# main_schematic.net
KiCad netlist of a schematic drawn in Altium Designer
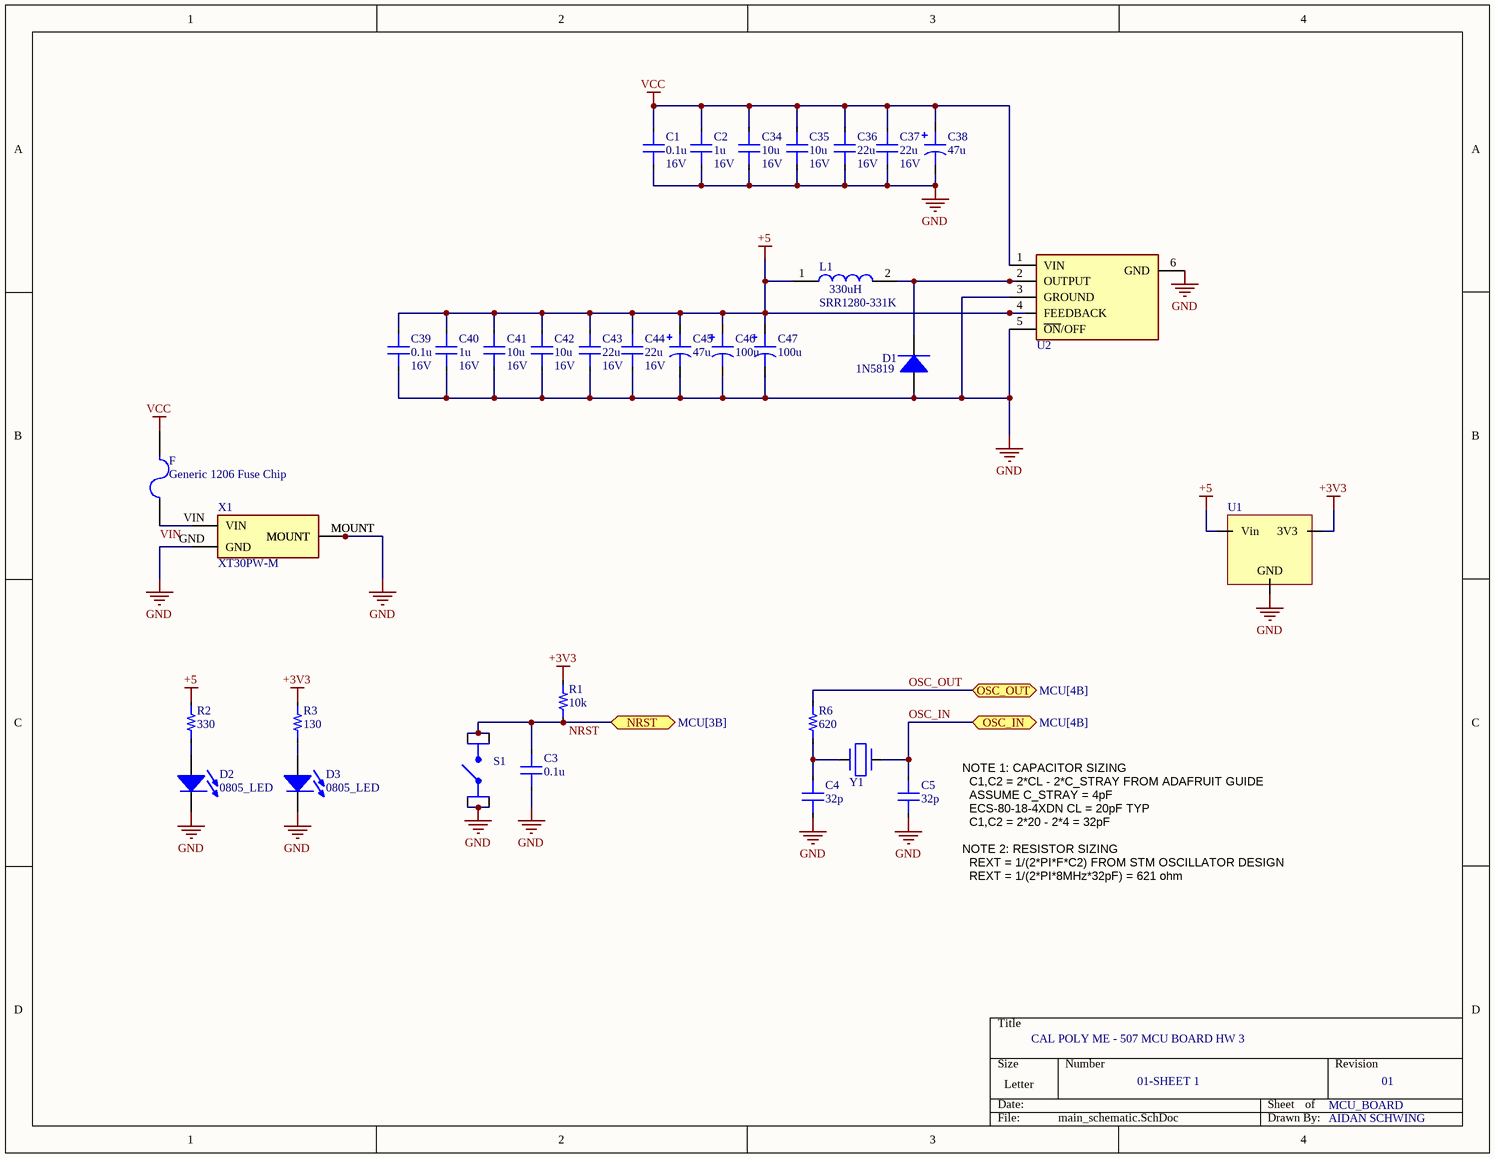
[diagram p0: main_schematic.SchDoc]

(export (version "E")
  (design (tool "Eeschema 10.0.6"))
  (components
    (comp (ref "C1")
      (value "0.1u")
      (footprint "0603_CAP")
      (fields (field (name "VOLTAGE") "16V") (field (name "Comment") "Capacitor"))
      (libsource (lib "Capacitors") (part "Capacitor"))
    )
    (comp (ref "C2")
      (value "1u")
      (footprint "0603_CAP")
      (fields (field (name "VOLTAGE") "16V") (field (name "Comment") "Capacitor"))
      (libsource (lib "Capacitors") (part "Capacitor"))
    )
    (comp (ref "C3")
      (value "0.1u")
      (footprint "0805_CAP")
      (fields (field (name "Comment") "Capacitor"))
      (libsource (lib "Capacitors") (part "Capacitor"))
    )
    (comp (ref "C4")
      (value "32p")
      (footprint "0805_CAP")
      (fields (field (name "Comment") "Capacitor"))
      (libsource (lib "Capacitors") (part "Capacitor"))
    )
    (comp (ref "C5")
      (value "32p")
      (footprint "0805_CAP")
      (fields (field (name "Comment") "Capacitor"))
      (libsource (lib "Capacitors") (part "Capacitor"))
    )
    (comp (ref "C34")
      (value "10u")
      (footprint "0805_CAP")
      (fields (field (name "VOLTAGE") "16V") (field (name "Comment") "Capacitor"))
      (libsource (lib "Capacitors") (part "Capacitor"))
    )
    (comp (ref "C35")
      (value "10u")
      (footprint "0805_CAP")
      (fields (field (name "VOLTAGE") "16V") (field (name "Comment") "Capacitor"))
      (libsource (lib "Capacitors") (part "Capacitor"))
    )
    (comp (ref "C36")
      (value "22u")
      (footprint "1210_CAP")
      (fields (field (name "VOLTAGE") "16V") (field (name "Comment") "Capacitor"))
      (libsource (lib "Capacitors") (part "Capacitor"))
    )
    (comp (ref "C37")
      (value "22u")
      (footprint "1210_CAP")
      (fields (field (name "VOLTAGE") "16V") (field (name "Comment") "Capacitor"))
      (libsource (lib "Capacitors") (part "Capacitor"))
    )
    (comp (ref "C38")
      (value "47u")
      (footprint "6.60x6.60x8.00mm_E_CAP")
      (fields (field (name "Comment") "UWT1H470MCL1GS"))
      (libsource (lib "Capacitors") (part "UWT1H470MCL1GS"))
    )
    (comp (ref "C39")
      (value "0.1u")
      (footprint "0603_CAP")
      (fields (field (name "VOLTAGE") "16V") (field (name "Comment") "Capacitor"))
      (libsource (lib "Capacitors") (part "Capacitor"))
    )
    (comp (ref "C40")
      (value "1u")
      (footprint "0603_CAP")
      (fields (field (name "VOLTAGE") "16V") (field (name "Comment") "Capacitor"))
      (libsource (lib "Capacitors") (part "Capacitor"))
    )
    (comp (ref "C41")
      (value "10u")
      (footprint "0805_CAP")
      (fields (field (name "VOLTAGE") "16V") (field (name "Comment") "Capacitor"))
      (libsource (lib "Capacitors") (part "Capacitor"))
    )
    (comp (ref "C42")
      (value "10u")
      (footprint "0805_CAP")
      (fields (field (name "VOLTAGE") "16V") (field (name "Comment") "Capacitor"))
      (libsource (lib "Capacitors") (part "Capacitor"))
    )
    (comp (ref "C43")
      (value "22u")
      (footprint "1210_CAP")
      (fields (field (name "VOLTAGE") "16V") (field (name "Comment") "Capacitor"))
      (libsource (lib "Capacitors") (part "Capacitor"))
    )
    (comp (ref "C44")
      (value "22u")
      (footprint "1210_CAP")
      (fields (field (name "VOLTAGE") "16V") (field (name "Comment") "Capacitor"))
      (libsource (lib "Capacitors") (part "Capacitor"))
    )
    (comp (ref "C45")
      (value "47u")
      (footprint "6.60x6.60x8.00mm_E_CAP")
      (fields (field (name "Comment") "UWT1H470MCL1GS"))
      (libsource (lib "Capacitors") (part "UWT1H470MCL1GS"))
    )
    (comp (ref "C46")
      (value "100u")
      (footprint "6.60x6.60x8.00mm_E_CAP")
      (description "CAP ALUM 100UF 20% 16V SMD")
      (fields (field (name "Comment") "865080343009"))
      (libsource (lib "Capacitors") (part "865080343009"))
    )
    (comp (ref "C47")
      (value "100u")
      (footprint "6.60x6.60x8.00mm_E_CAP")
      (description "CAP ALUM 100UF 20% 16V SMD")
      (fields (field (name "Comment") "865080343009"))
      (libsource (lib "Capacitors") (part "865080343009"))
    )
    (comp (ref "D1")
      (value "1N5819")
      (footprint "SOD-123F")
      (description "Diode Super Barrier 40V 1A Surface Mount SOD-123F")
      (libsource (lib "Diodes") (part "1N5819"))
    )
    (comp (ref "D2")
      (value "0805_LED")
      (footprint "0805_LED")
      (description "Generic 0805 LED")
      (libsource (lib "Diodes") (part "0805_LED"))
    )
    (comp (ref "D3")
      (value "0805_LED")
      (footprint "0805_LED")
      (description "Generic 0805 LED")
      (libsource (lib "Diodes") (part "0805_LED"))
    )
    (comp (ref "F")
      (value "Generic 1206 Fuse Chip")
      (footprint "1206_RES")
      (libsource (lib "Fuses") (part "Generic 1206 Fuse Chip"))
    )
    (comp (ref "L1")
      (value "SRR1280-331K")
      (footprint "SRR1280-150M")
      (description "Power Inductors - SMD 330uH 10% SMD 1280")
      (fields (field (name "MFRPARTNO") "652-SRR1280-331K"))
      (libsource (lib "Magnetic") (part "SRR1280-331K"))
    )
    (comp (ref "R1")
      (value "10k")
      (footprint "0603_RES")
      (fields (field (name "Comment") "Resistor"))
      (libsource (lib "Resistors") (part "Resistor"))
    )
    (comp (ref "R2")
      (value "330")
      (footprint "0603_RES")
      (fields (field (name "Comment") "Resistor"))
      (libsource (lib "Resistors") (part "Resistor"))
    )
    (comp (ref "R3")
      (value "130")
      (footprint "0603_RES")
      (fields (field (name "Comment") "Resistor"))
      (libsource (lib "Resistors") (part "Resistor"))
    )
    (comp (ref "R6")
      (value "620")
      (footprint "0805_RES")
      (fields (field (name "Comment") "Resistor"))
      (libsource (lib "Resistors") (part "Resistor"))
    )
    (comp (ref "S1")
      (value "TactileSwitch")
      (footprint "6mmTactileSwitch_ThroughHole")
      (description "Generic 6mm Through Hole Tactile Switch")
      (libsource (lib "ElectroMechanical") (part "TactileSwitch"))
    )
    (comp (ref "U1")
      (value "~")
      (footprint "DPAK3_TO-252-3")
      (description "IC REG LINEAR 3.3V 1A DPAK")
      (libsource (lib "Power") (part "NCP1117DT33T5G"))
    )
    (comp (ref "U2")
      (value "LM2576-5.0WU")
      (footprint "MICROCHIP_TO-263")
      (description "Switching Voltage Regulators 3A Step-Down SMPS Regulator")
      (fields (field (name "MOUSER PART NUMBER") "998-LM2576-5.0WU"))
      (libsource (lib "Power") (part "LM2576-5.0WU"))
    )
    (comp (ref "X1")
      (value "XT30PW-M")
      (footprint "XT30PWM")
      (description "Socket; DC supply; XT30; male; PIN: 2; on PCBs; THT; yellow; 15A; 500V")
      (libsource (lib "Connectors") (part "XT30PW-M"))
    )
    (comp (ref "Y1")
      (value "ECS-80-18-4XDN")
      (footprint "ECS-80-18")
      (description "Crystals 8MHz 18pF EX/TEMP HC-49US")
      (libsource (lib "Analog_IC") (part "ECS-80-18-4XDN"))
    )
  )
  (nets
    (net (code "1") (name "+3V3") (class "Default")
      (node (ref "R1") (pin "2") (pinfunction "2_2") (pintype "passive"))
      (node (ref "R3") (pin "2") (pinfunction "2_2") (pintype "passive"))
      (node (ref "U1") (pin "4") (pinfunction "3V3_4") (pintype "passive"))
    )
    (net (code "2") (name "+5") (class "Default")
      (node (ref "C39") (pin "1") (pinfunction "1_1") (pintype "passive"))
      (node (ref "C40") (pin "1") (pinfunction "1_1") (pintype "passive"))
      (node (ref "C41") (pin "1") (pinfunction "1_1") (pintype "passive"))
      (node (ref "C42") (pin "1") (pinfunction "1_1") (pintype "passive"))
      (node (ref "C43") (pin "1") (pinfunction "1_1") (pintype "passive"))
      (node (ref "C44") (pin "1") (pinfunction "1_1") (pintype "passive"))
      (node (ref "C45") (pin "1") (pinfunction "1_1") (pintype "passive"))
      (node (ref "C46") (pin "1") (pinfunction "1_1") (pintype "passive"))
      (node (ref "C47") (pin "1") (pinfunction "1_1") (pintype "passive"))
      (node (ref "L1") (pin "1") (pinfunction "1_1") (pintype "passive"))
      (node (ref "R2") (pin "2") (pinfunction "2_2") (pintype "passive"))
      (node (ref "U1") (pin "3") (pinfunction "Vin_3") (pintype "passive"))
      (node (ref "U2") (pin "4") (pinfunction "FEEDBACK_4") (pintype "passive"))
    )
    (net (code "3") (name "/NRST") (class "Default")
      (node (ref "C3") (pin "2") (pinfunction "2_2") (pintype "passive"))
      (node (ref "R1") (pin "1") (pinfunction "1_1") (pintype "passive"))
      (node (ref "S1") (pin "3") (pinfunction "3_3") (pintype "passive"))
      (node (ref "S1") (pin "4") (pinfunction "4_4") (pintype "passive"))
    )
    (net (code "4") (name "/OSC_IN") (class "Default")
      (node (ref "C5") (pin "2") (pinfunction "2_2") (pintype "passive"))
      (node (ref "Y1") (pin "2") (pinfunction "2_2") (pintype "passive"))
    )
    (net (code "5") (name "/OSC_OUT") (class "Default")
      (node (ref "R6") (pin "2") (pinfunction "2_2") (pintype "passive"))
    )
    (net (code "6") (name "/VIN") (class "Default")
      (node (ref "F") (pin "1") (pinfunction "1_1") (pintype "passive"))
      (node (ref "X1") (pin "VIN") (pinfunction "VIN_VIN") (pintype "passive"))
    )
    (net (code "7") (name "GND") (class "Default")
      (node (ref "C1") (pin "2") (pinfunction "2_2") (pintype "passive"))
      (node (ref "C2") (pin "2") (pinfunction "2_2") (pintype "passive"))
      (node (ref "C3") (pin "1") (pinfunction "1_1") (pintype "passive"))
      (node (ref "C34") (pin "2") (pinfunction "2_2") (pintype "passive"))
      (node (ref "C35") (pin "2") (pinfunction "2_2") (pintype "passive"))
      (node (ref "C36") (pin "2") (pinfunction "2_2") (pintype "passive"))
      (node (ref "C37") (pin "2") (pinfunction "2_2") (pintype "passive"))
      (node (ref "C38") (pin "2") (pinfunction "2_2") (pintype "passive"))
      (node (ref "C39") (pin "2") (pinfunction "2_2") (pintype "passive"))
      (node (ref "C4") (pin "1") (pinfunction "1_1") (pintype "passive"))
      (node (ref "C40") (pin "2") (pinfunction "2_2") (pintype "passive"))
      (node (ref "C41") (pin "2") (pinfunction "2_2") (pintype "passive"))
      (node (ref "C42") (pin "2") (pinfunction "2_2") (pintype "passive"))
      (node (ref "C43") (pin "2") (pinfunction "2_2") (pintype "passive"))
      (node (ref "C44") (pin "2") (pinfunction "2_2") (pintype "passive"))
      (node (ref "C45") (pin "2") (pinfunction "2_2") (pintype "passive"))
      (node (ref "C46") (pin "2") (pinfunction "2_2") (pintype "passive"))
      (node (ref "C47") (pin "2") (pinfunction "2_2") (pintype "passive"))
      (node (ref "C5") (pin "1") (pinfunction "1_1") (pintype "passive"))
      (node (ref "D1") (pin "2") (pintype "passive"))
      (node (ref "D2") (pin "2") (pinfunction "K_2") (pintype "passive"))
      (node (ref "D3") (pin "2") (pinfunction "K_2") (pintype "passive"))
      (node (ref "S1") (pin "1") (pinfunction "1_1") (pintype "passive"))
      (node (ref "S1") (pin "2") (pinfunction "2_2") (pintype "passive"))
      (node (ref "U1") (pin "1") (pinfunction "GND_1") (pintype "passive"))
      (node (ref "U2") (pin "3") (pinfunction "GROUND_3") (pintype "passive"))
      (node (ref "U2") (pin "5") (pinfunction "~{ON}/OFF_5") (pintype "passive"))
      (node (ref "U2") (pin "6") (pinfunction "GND_6") (pintype "passive"))
      (node (ref "X1") (pin "GND") (pinfunction "GND_GND") (pintype "passive"))
      (node (ref "X1") (pin "MOUNT") (pinfunction "MOUNT_MOUNT") (pintype "passive"))
    )
    (net (code "8") (name "Net-(C4-Pad2)") (class "Default")
      (node (ref "C4") (pin "2") (pinfunction "2_2") (pintype "passive"))
      (node (ref "R6") (pin "1") (pinfunction "1_1") (pintype "passive"))
      (node (ref "Y1") (pin "1") (pinfunction "1_1") (pintype "passive"))
    )
    (net (code "9") (name "Net-(D2-A)") (class "Default")
      (node (ref "D2") (pin "1") (pinfunction "A_1") (pintype "passive"))
      (node (ref "R2") (pin "1") (pinfunction "1_1") (pintype "passive"))
    )
    (net (code "10") (name "Net-(D3-A)") (class "Default")
      (node (ref "D3") (pin "1") (pinfunction "A_1") (pintype "passive"))
      (node (ref "R3") (pin "1") (pinfunction "1_1") (pintype "passive"))
    )
    (net (code "11") (name "Net-(U2-OUTPUT)") (class "Default")
      (node (ref "D1") (pin "1") (pintype "passive"))
      (node (ref "L1") (pin "2") (pinfunction "2_2") (pintype "passive"))
      (node (ref "U2") (pin "2") (pinfunction "OUTPUT_2") (pintype "passive"))
    )
    (net (code "12") (name "VCC") (class "Default")
      (node (ref "C1") (pin "1") (pinfunction "1_1") (pintype "passive"))
      (node (ref "C2") (pin "1") (pinfunction "1_1") (pintype "passive"))
      (node (ref "C34") (pin "1") (pinfunction "1_1") (pintype "passive"))
      (node (ref "C35") (pin "1") (pinfunction "1_1") (pintype "passive"))
      (node (ref "C36") (pin "1") (pinfunction "1_1") (pintype "passive"))
      (node (ref "C37") (pin "1") (pinfunction "1_1") (pintype "passive"))
      (node (ref "C38") (pin "1") (pinfunction "1_1") (pintype "passive"))
      (node (ref "F") (pin "2") (pinfunction "2_2") (pintype "passive"))
      (node (ref "U2") (pin "1") (pinfunction "VIN_1") (pintype "passive"))
    )
  )
)
